# For_LCD5110.net
KiCad netlist of a schematic drawn in Altium Designer
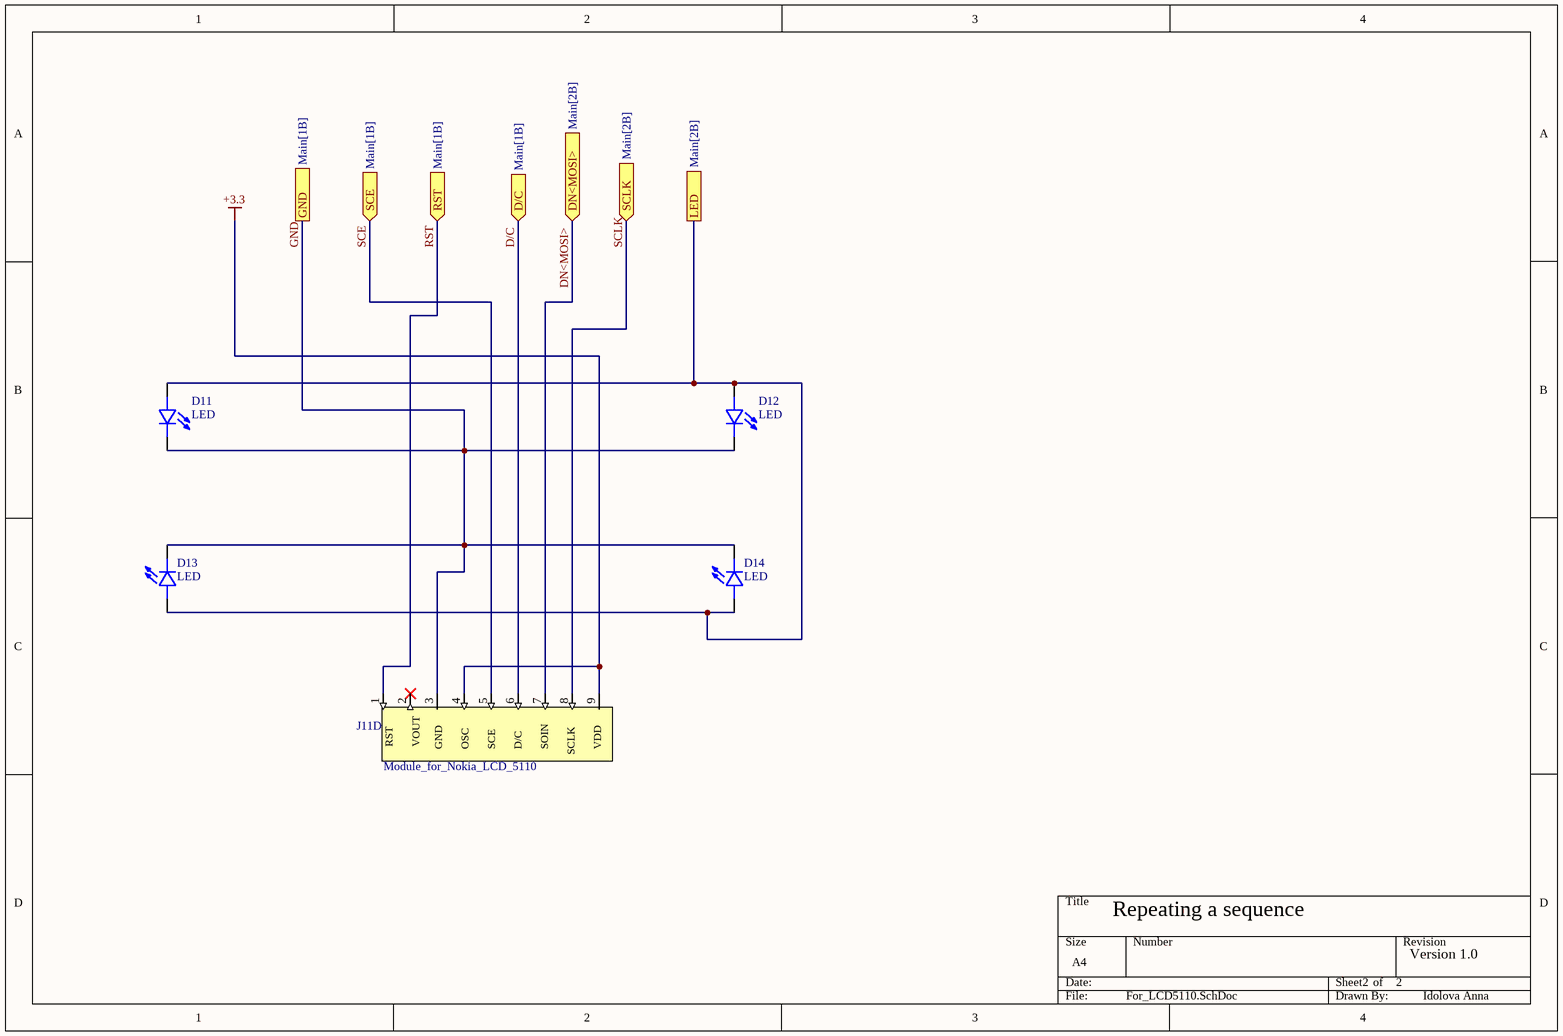
[diagram p0: For_LCD5110.SchDoc]

(export (version "E")
  (design (tool "Eeschema 10.0.6"))
  (components
    (comp (ref "D11")
      (value "LED")
      (footprint "LED_LTW-170TK")
      (description "White - LED Indication - Discrete 3.3V 0805 (2012 Metric)")
      (fields (field (name "MF") "Lite-On Inc.") (field (name "MP") "LTW-170TK"))
      (libsource (lib "") (part "LTW-170TK_1"))
    )
    (comp (ref "D12")
      (value "LED")
      (footprint "LED_LTW-170TK")
      (description "White - LED Indication - Discrete 3.3V 0805 (2012 Metric)")
      (fields (field (name "MF") "Lite-On Inc.") (field (name "MP") "LTW-170TK"))
      (libsource (lib "") (part "LTW-170TK_1"))
    )
    (comp (ref "D13")
      (value "LED")
      (footprint "LED_LTW-170TK")
      (description "White - LED Indication - Discrete 3.3V 0805 (2012 Metric)")
      (fields (field (name "MF") "Lite-On Inc.") (field (name "MP") "LTW-170TK"))
      (libsource (lib "National Technical University of Ukraine Igor Sikorsky Kyiv Polytechnic Institute- Educator Program") (part "LTW-170TK"))
    )
    (comp (ref "D14")
      (value "LED")
      (footprint "LED_LTW-170TK")
      (description "White - LED Indication - Discrete 3.3V 0805 (2012 Metric)")
      (fields (field (name "MF") "Lite-On Inc.") (field (name "MP") "LTW-170TK"))
      (libsource (lib "National Technical University of Ukraine Igor Sikorsky Kyiv Polytechnic Institute- Educator Program") (part "LTW-170TK"))
    )
    (comp (ref "J11")
      (value "Module_for_Nokia_LCD_5110")
      (footprint "PCBComponent_1")
      (libsource (lib "Module") (part "Module_for_Nokia_LCD_5110"))
    )
  )
  (nets
    (net (code "1") (name "+3.3") (class "Default")
      (node (ref "J11") (pin "4") (pinfunction "4_4") (pintype "input"))
      (node (ref "J11") (pin "9") (pinfunction "9_9") (pintype "power_in"))
    )
    (net (code "2") (name "/DN<MOSI>") (class "Default")
      (node (ref "J11") (pin "7") (pinfunction "7_7") (pintype "input"))
    )
    (net (code "3") (name "/D{slash}C") (class "Default")
      (node (ref "J11") (pin "6") (pinfunction "6_6") (pintype "input"))
    )
    (net (code "4") (name "/GND") (class "Default")
      (node (ref "D11") (pin "C") (pinfunction "C_C") (pintype "passive"))
      (node (ref "D12") (pin "C") (pinfunction "C_C") (pintype "passive"))
      (node (ref "D13") (pin "C") (pinfunction "C_C") (pintype "passive"))
      (node (ref "D14") (pin "C") (pinfunction "C_C") (pintype "passive"))
      (node (ref "J11") (pin "3") (pinfunction "3_3") (pintype "power_in"))
    )
    (net (code "5") (name "/LED") (class "Default")
      (node (ref "D11") (pin "A") (pinfunction "A_A") (pintype "passive"))
      (node (ref "D12") (pin "A") (pinfunction "A_A") (pintype "passive"))
      (node (ref "D13") (pin "A") (pinfunction "A_A") (pintype "passive"))
      (node (ref "D14") (pin "A") (pinfunction "A_A") (pintype "passive"))
    )
    (net (code "6") (name "/RST") (class "Default")
      (node (ref "J11") (pin "1") (pinfunction "1_1") (pintype "input"))
    )
    (net (code "7") (name "/SCE") (class "Default")
      (node (ref "J11") (pin "5") (pinfunction "5_5") (pintype "input"))
    )
    (net (code "8") (name "/SCLK") (class "Default")
      (node (ref "J11") (pin "8") (pinfunction "8_8") (pintype "input"))
    )
    (net (code "9") (name "unconnected-(J11-Pad2)") (class "Default")
      (node (ref "J11") (pin "2") (pinfunction "2_2") (pintype "output+no_connect"))
    )
  )
)
